# 1-Schematic_Nakuja_Remix_4.net
KiCad netlist of a schematic drawn in EasyEDA
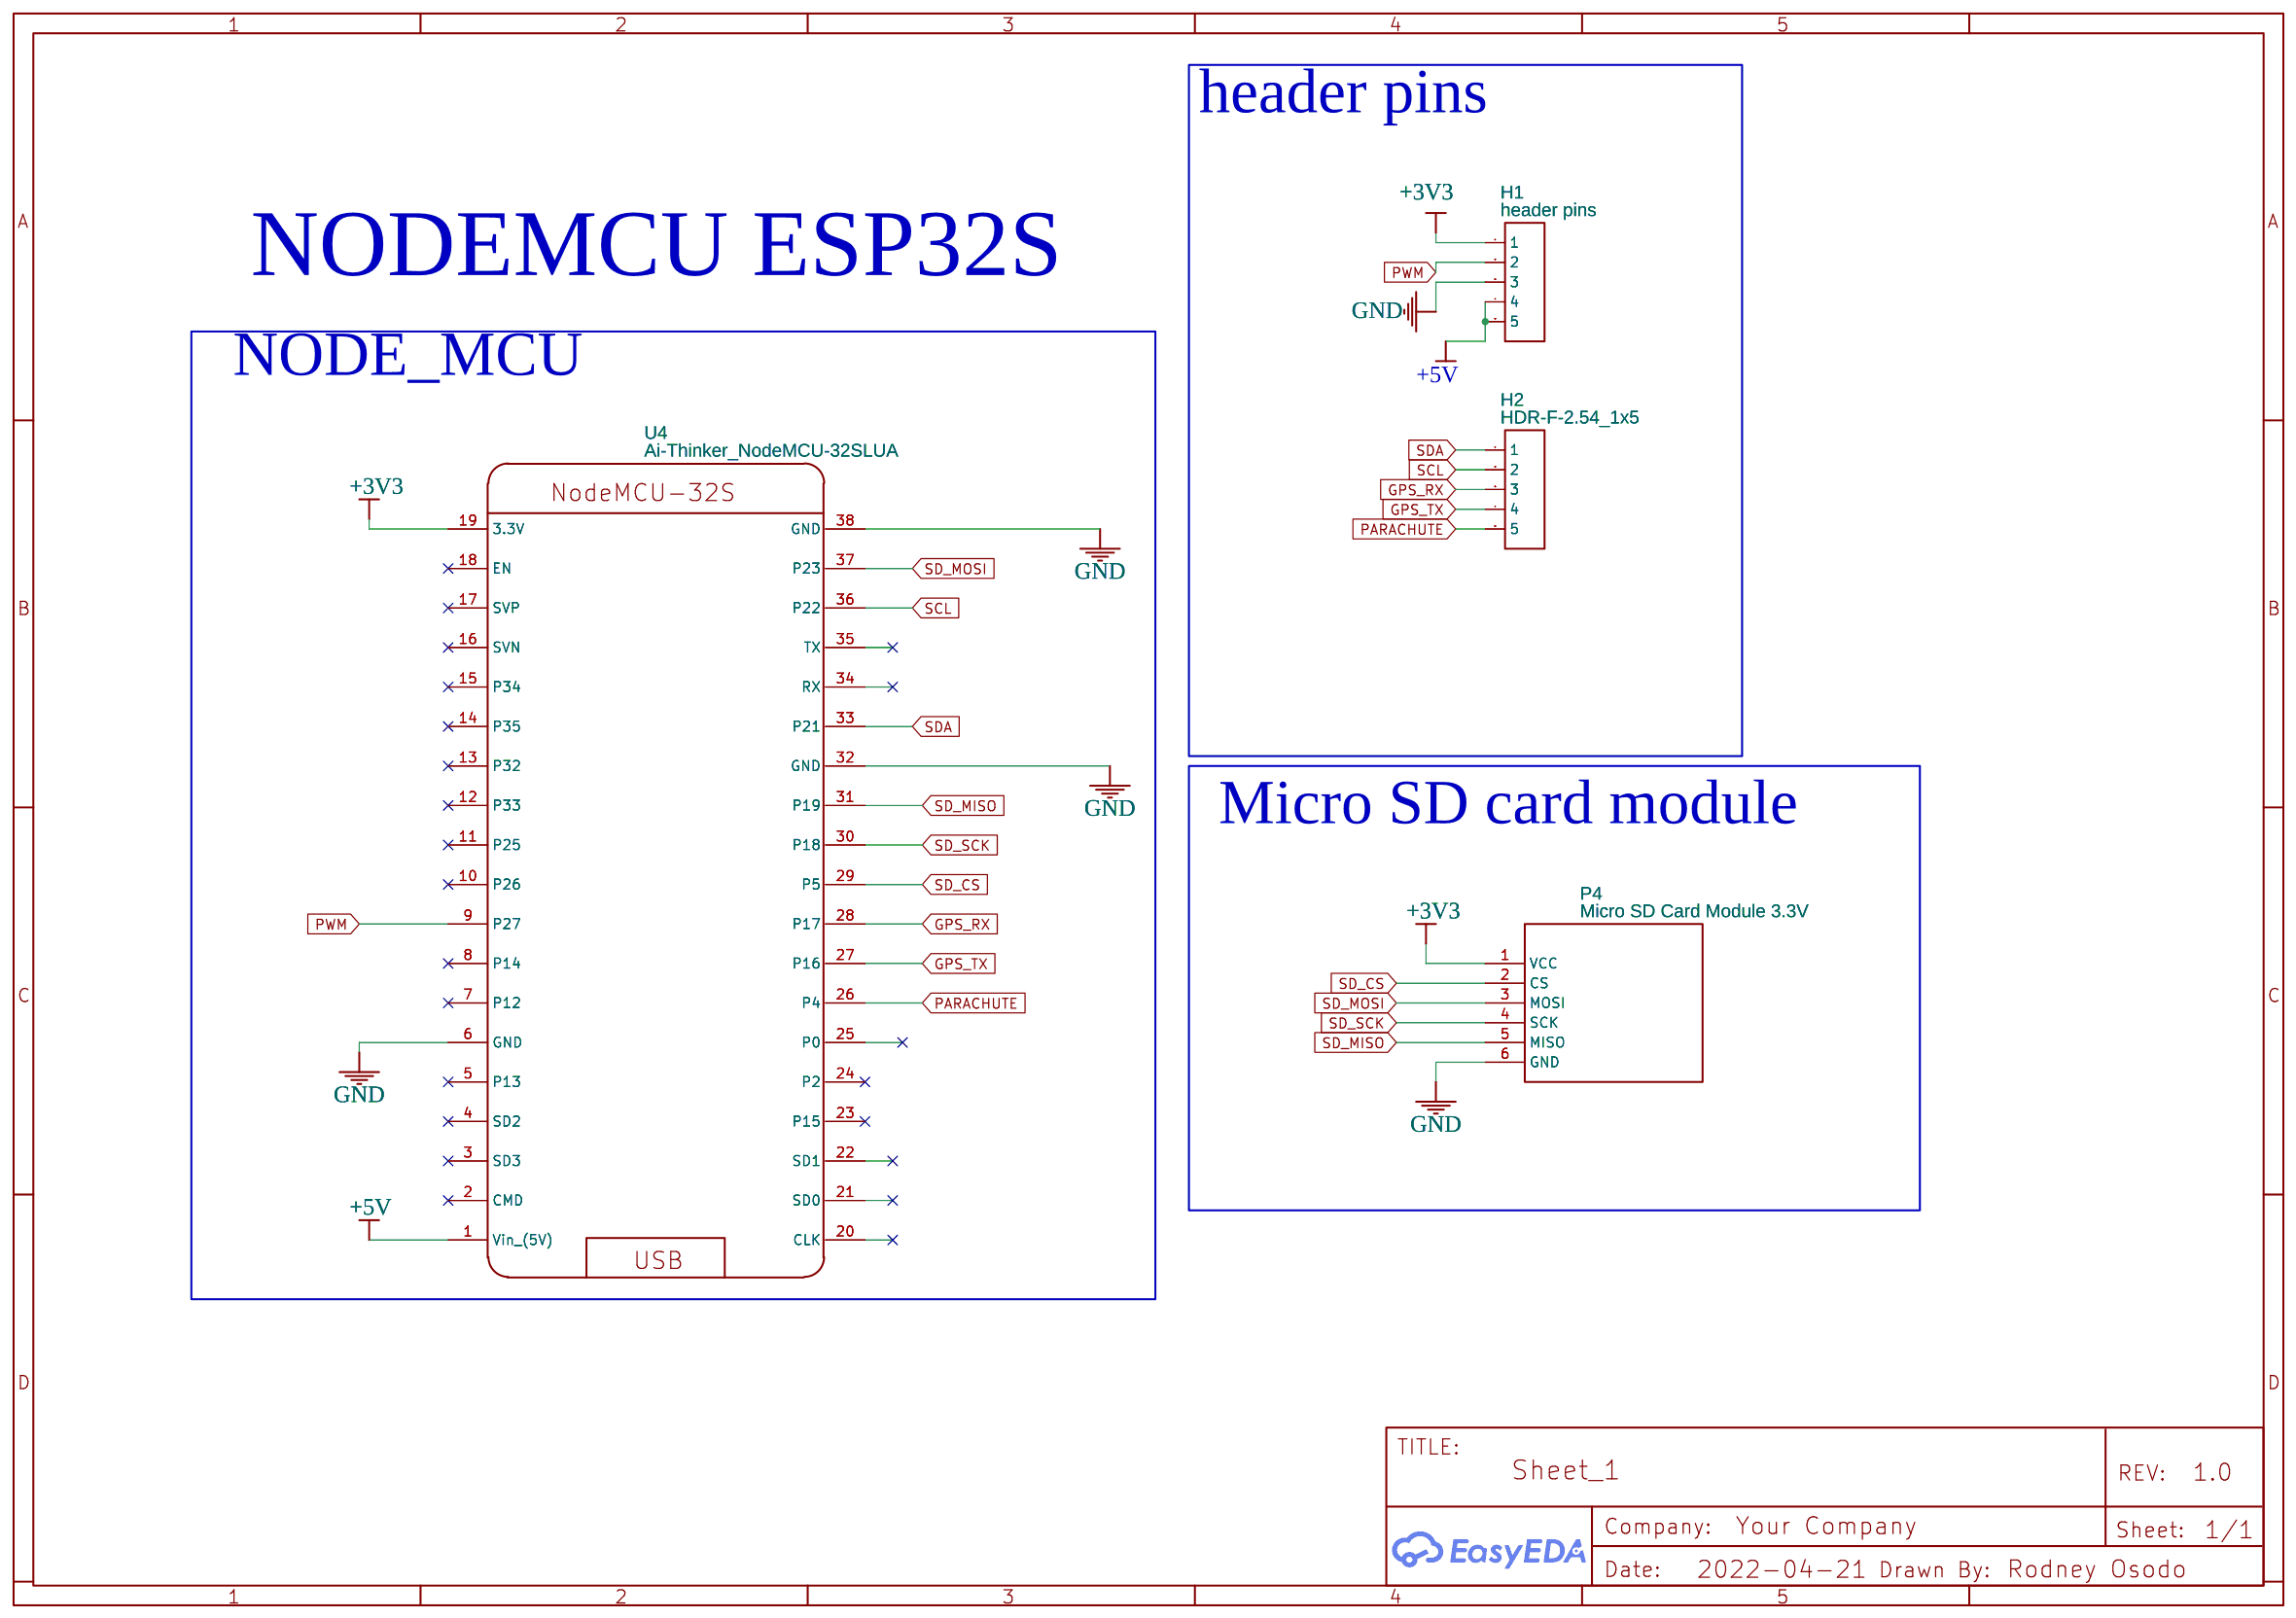
[diagram p0: schematic sheet]

(export (version "E")
  (design (tool "Eeschema 10.0.6"))
  (components
    (comp (ref "H1")
      (value "header pins")
      (fields (field (name "BOM_Supplier Part") "C50950"))
      (libsource (lib "") (part "HDR-F-2.54_1x5"))
    )
    (comp (ref "H2")
      (value "HDR-F-2.54_1x5")
      (fields (field (name "BOM_Supplier Part") "C50950"))
      (libsource (lib "") (part "HDR-F-2.54_1x5"))
    )
    (comp (ref "P4")
      (value "Micro SD Card Module 3.3V")
      (libsource (lib "") (part "Micro SD Card Module 3.3V"))
    )
    (comp (ref "U4")
      (value "Ai-Thinker_NodeMCU-32SLUA")
      (fields
        (field (name "BOM_Manufacturer Part") "NodeMCU-32SLua")
        (field (name "BOM_Supplier Part") "C111436")
      )
      (libsource (lib "") (part "Ai-Thinker_NodeMCU-32SLUA"))
    )
  )
  (nets
    (net (code "1") (name "+3V3") (class "Default")
      (node (ref "H1") (pin "1") (pinfunction "1_1") (pintype "unspecified"))
      (node (ref "P4") (pin "1") (pinfunction "VCC_1") (pintype "unspecified"))
      (node (ref "U4") (pin "19") (pinfunction "3.3V_19") (pintype "unspecified"))
    )
    (net (code "2") (name "+5V") (class "Default")
      (node (ref "H1") (pin "4") (pinfunction "4_4") (pintype "unspecified"))
      (node (ref "H1") (pin "5") (pinfunction "5_5") (pintype "unspecified"))
      (node (ref "U4") (pin "1") (pinfunction "Vin_(5V)_1") (pintype "unspecified"))
    )
    (net (code "3") (name "GND") (class "Default")
      (node (ref "H1") (pin "3") (pinfunction "3_3") (pintype "unspecified"))
      (node (ref "P4") (pin "6") (pinfunction "GND_6") (pintype "unspecified"))
      (node (ref "U4") (pin "32") (pinfunction "GND_32") (pintype "unspecified"))
      (node (ref "U4") (pin "38") (pinfunction "GND_38") (pintype "unspecified"))
      (node (ref "U4") (pin "6") (pinfunction "GND_6") (pintype "unspecified"))
    )
    (net (code "4") (name "GPS_RX") (class "Default")
      (node (ref "H2") (pin "3") (pinfunction "3_3") (pintype "unspecified"))
      (node (ref "U4") (pin "28") (pinfunction "P17_28") (pintype "unspecified"))
    )
    (net (code "5") (name "GPS_TX") (class "Default")
      (node (ref "H2") (pin "4") (pinfunction "4_4") (pintype "unspecified"))
      (node (ref "U4") (pin "27") (pinfunction "P16_27") (pintype "unspecified"))
    )
    (net (code "6") (name "PARACHUTE") (class "Default")
      (node (ref "H2") (pin "5") (pinfunction "5_5") (pintype "unspecified"))
      (node (ref "U4") (pin "26") (pinfunction "P4_26") (pintype "unspecified"))
    )
    (net (code "7") (name "PWM") (class "Default")
      (node (ref "H1") (pin "2") (pinfunction "2_2") (pintype "unspecified"))
      (node (ref "U4") (pin "9") (pinfunction "P27_9") (pintype "unspecified"))
    )
    (net (code "8") (name "SCL") (class "Default")
      (node (ref "H2") (pin "2") (pinfunction "2_2") (pintype "unspecified"))
      (node (ref "U4") (pin "36") (pinfunction "P22_36") (pintype "unspecified"))
    )
    (net (code "9") (name "SDA") (class "Default")
      (node (ref "H2") (pin "1") (pinfunction "1_1") (pintype "unspecified"))
      (node (ref "U4") (pin "33") (pinfunction "P21_33") (pintype "unspecified"))
    )
    (net (code "10") (name "SD_CS") (class "Default")
      (node (ref "P4") (pin "2") (pinfunction "CS_2") (pintype "unspecified"))
      (node (ref "U4") (pin "29") (pinfunction "P5_29") (pintype "unspecified"))
    )
    (net (code "11") (name "SD_MISO") (class "Default")
      (node (ref "P4") (pin "5") (pinfunction "MISO_5") (pintype "unspecified"))
      (node (ref "U4") (pin "31") (pinfunction "P19_31") (pintype "unspecified"))
    )
    (net (code "12") (name "SD_MOSI") (class "Default")
      (node (ref "P4") (pin "3") (pinfunction "MOSI_3") (pintype "unspecified"))
      (node (ref "U4") (pin "37") (pinfunction "P23_37") (pintype "unspecified"))
    )
    (net (code "13") (name "SD_SCK") (class "Default")
      (node (ref "P4") (pin "4") (pinfunction "SCK_4") (pintype "unspecified"))
      (node (ref "U4") (pin "30") (pinfunction "P18_30") (pintype "unspecified"))
    )
    (net (code "14") (name "unconnected-(U4-CLK-Pad20)") (class "Default")
      (node (ref "U4") (pin "20") (pinfunction "CLK_20") (pintype "unspecified+no_connect"))
    )
    (net (code "15") (name "unconnected-(U4-CMD-Pad2)") (class "Default")
      (node (ref "U4") (pin "2") (pinfunction "CMD_2") (pintype "unspecified+no_connect"))
    )
    (net (code "16") (name "unconnected-(U4-EN-Pad18)") (class "Default")
      (node (ref "U4") (pin "18") (pinfunction "EN_18") (pintype "unspecified+no_connect"))
    )
    (net (code "17") (name "unconnected-(U4-P0-Pad25)") (class "Default")
      (node (ref "U4") (pin "25") (pinfunction "P0_25") (pintype "unspecified+no_connect"))
    )
    (net (code "18") (name "unconnected-(U4-P2-Pad24)") (class "Default")
      (node (ref "U4") (pin "24") (pinfunction "P2_24") (pintype "unspecified+no_connect"))
    )
    (net (code "19") (name "unconnected-(U4-P12-Pad7)") (class "Default")
      (node (ref "U4") (pin "7") (pinfunction "P12_7") (pintype "unspecified+no_connect"))
    )
    (net (code "20") (name "unconnected-(U4-P13-Pad5)") (class "Default")
      (node (ref "U4") (pin "5") (pinfunction "P13_5") (pintype "unspecified+no_connect"))
    )
    (net (code "21") (name "unconnected-(U4-P14-Pad8)") (class "Default")
      (node (ref "U4") (pin "8") (pinfunction "P14_8") (pintype "unspecified+no_connect"))
    )
    (net (code "22") (name "unconnected-(U4-P15-Pad23)") (class "Default")
      (node (ref "U4") (pin "23") (pinfunction "P15_23") (pintype "unspecified+no_connect"))
    )
    (net (code "23") (name "unconnected-(U4-P25-Pad11)") (class "Default")
      (node (ref "U4") (pin "11") (pinfunction "P25_11") (pintype "unspecified+no_connect"))
    )
    (net (code "24") (name "unconnected-(U4-P26-Pad10)") (class "Default")
      (node (ref "U4") (pin "10") (pinfunction "P26_10") (pintype "unspecified+no_connect"))
    )
    (net (code "25") (name "unconnected-(U4-P32-Pad13)") (class "Default")
      (node (ref "U4") (pin "13") (pinfunction "P32_13") (pintype "unspecified+no_connect"))
    )
    (net (code "26") (name "unconnected-(U4-P33-Pad12)") (class "Default")
      (node (ref "U4") (pin "12") (pinfunction "P33_12") (pintype "unspecified+no_connect"))
    )
    (net (code "27") (name "unconnected-(U4-P34-Pad15)") (class "Default")
      (node (ref "U4") (pin "15") (pinfunction "P34_15") (pintype "unspecified+no_connect"))
    )
    (net (code "28") (name "unconnected-(U4-P35-Pad14)") (class "Default")
      (node (ref "U4") (pin "14") (pinfunction "P35_14") (pintype "unspecified+no_connect"))
    )
    (net (code "29") (name "unconnected-(U4-RX-Pad34)") (class "Default")
      (node (ref "U4") (pin "34") (pinfunction "RX_34") (pintype "unspecified+no_connect"))
    )
    (net (code "30") (name "unconnected-(U4-SD0-Pad21)") (class "Default")
      (node (ref "U4") (pin "21") (pinfunction "SD0_21") (pintype "unspecified+no_connect"))
    )
    (net (code "31") (name "unconnected-(U4-SD1-Pad22)") (class "Default")
      (node (ref "U4") (pin "22") (pinfunction "SD1_22") (pintype "unspecified+no_connect"))
    )
    (net (code "32") (name "unconnected-(U4-SD2-Pad4)") (class "Default")
      (node (ref "U4") (pin "4") (pinfunction "SD2_4") (pintype "unspecified+no_connect"))
    )
    (net (code "33") (name "unconnected-(U4-SD3-Pad3)") (class "Default")
      (node (ref "U4") (pin "3") (pinfunction "SD3_3") (pintype "unspecified+no_connect"))
    )
    (net (code "34") (name "unconnected-(U4-SVN-Pad16)") (class "Default")
      (node (ref "U4") (pin "16") (pinfunction "SVN_16") (pintype "unspecified+no_connect"))
    )
    (net (code "35") (name "unconnected-(U4-SVP-Pad17)") (class "Default")
      (node (ref "U4") (pin "17") (pinfunction "SVP_17") (pintype "unspecified+no_connect"))
    )
    (net (code "36") (name "unconnected-(U4-TX-Pad35)") (class "Default")
      (node (ref "U4") (pin "35") (pinfunction "TX_35") (pintype "unspecified+no_connect"))
    )
  )
)
